# RTC_and_EEPROM.net
KiCad netlist of a schematic drawn in Altium Designer
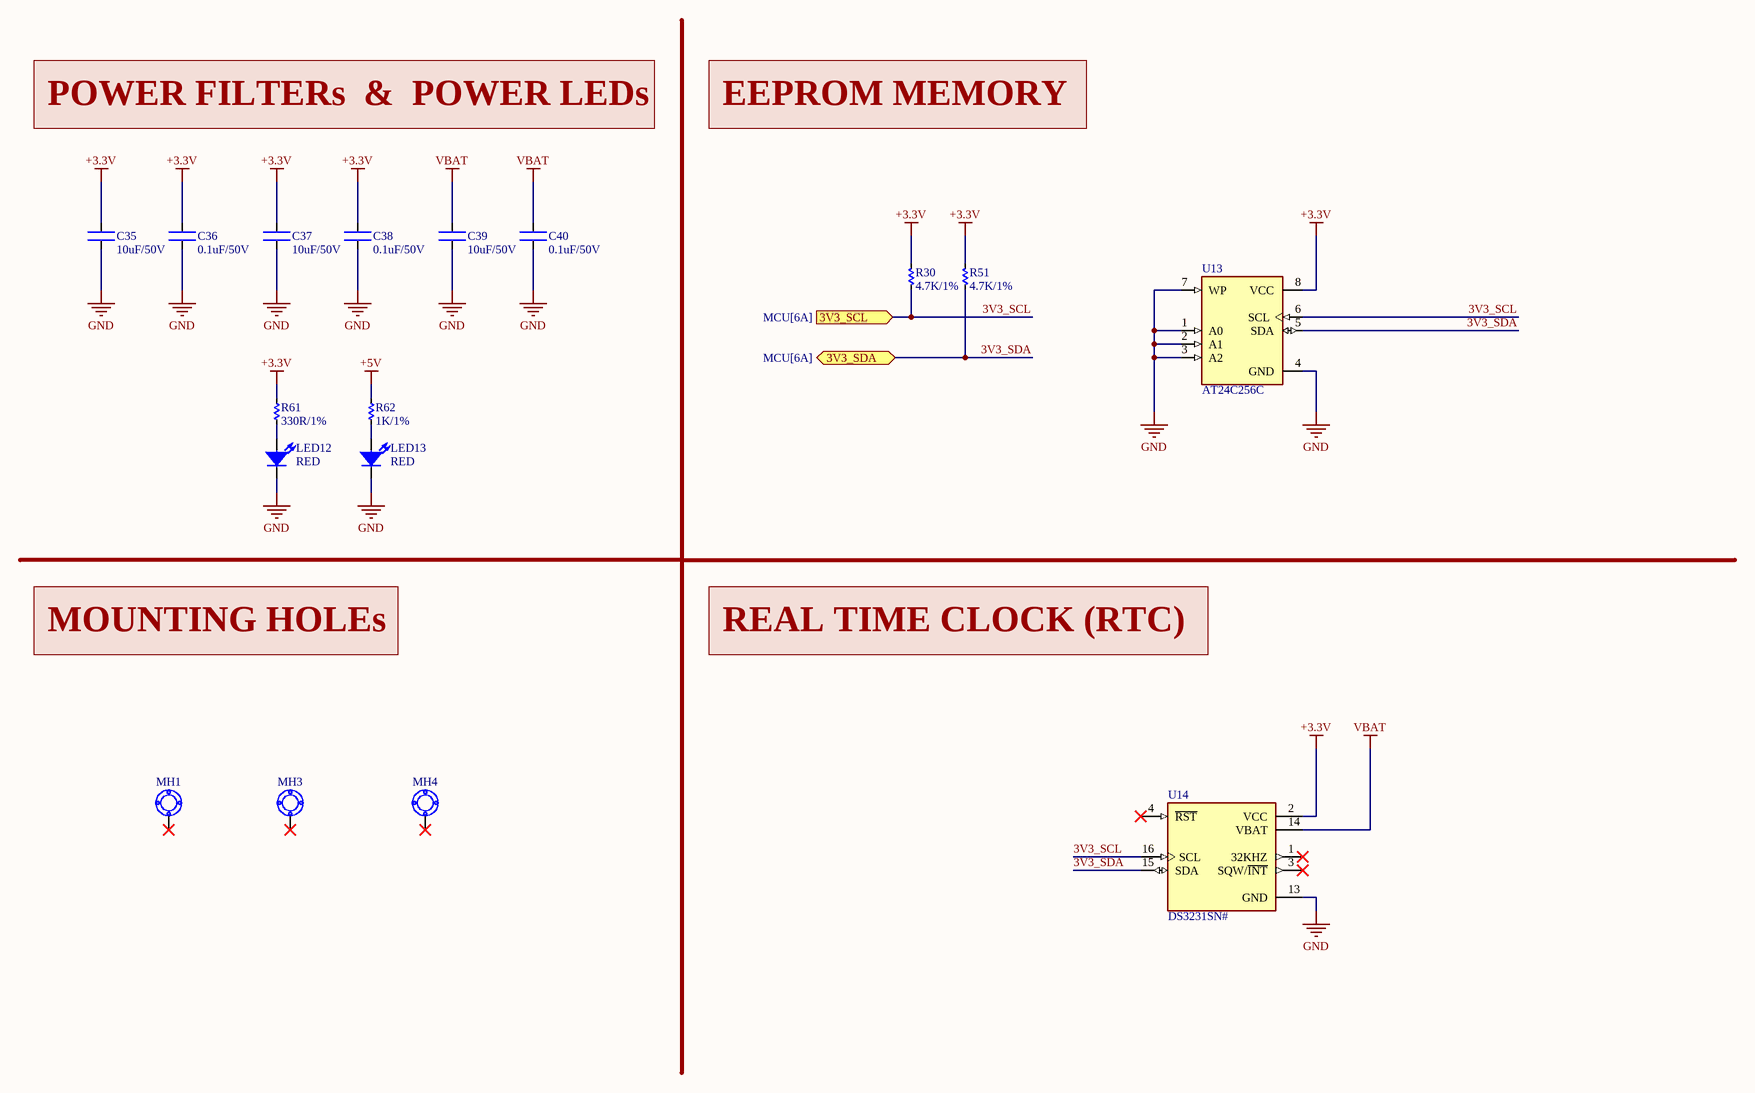
[diagram p0: RTC_and_EEPROM.SchDoc]

(export (version "E")
  (design (tool "Eeschema 10.0.6"))
  (components
    (comp (ref "C35")
      (value "10uF/50V")
      (footprint "CAP - 0603")
      (description "CAPACITOR SMD - KEMET")
      (libsource (lib "NewLibrary") (part "CAPACITOR"))
    )
    (comp (ref "C36")
      (value "0.1uF/50V")
      (footprint "CAP - 0603")
      (description "CAPACITOR SMD - KEMET")
      (libsource (lib "NewLibrary") (part "CAPACITOR"))
    )
    (comp (ref "C37")
      (value "10uF/50V")
      (footprint "CAP - 0603")
      (description "CAPACITOR SMD - KEMET")
      (libsource (lib "NewLibrary") (part "CAPACITOR"))
    )
    (comp (ref "C38")
      (value "0.1uF/50V")
      (footprint "CAP - 0603")
      (description "CAPACITOR SMD - KEMET")
      (libsource (lib "NewLibrary") (part "CAPACITOR"))
    )
    (comp (ref "C39")
      (value "10uF/50V")
      (footprint "CAP - 0603")
      (description "CAPACITOR SMD - KEMET")
      (libsource (lib "NewLibrary") (part "CAPACITOR"))
    )
    (comp (ref "C40")
      (value "0.1uF/50V")
      (footprint "CAP - 0603")
      (description "CAPACITOR SMD - KEMET")
      (libsource (lib "NewLibrary") (part "CAPACITOR"))
    )
    (comp (ref "LED12")
      (value "RED")
      (footprint "RED_LED_0603")
      (description "LED SMD")
      (libsource (lib "NewLibrary") (part "LED_SMD"))
    )
    (comp (ref "LED13")
      (value "RED")
      (footprint "RED_LED_0603")
      (description "LED SMD")
      (libsource (lib "NewLibrary") (part "LED_SMD"))
    )
    (comp (ref "MH1")
      (value "MOUNTING HOLE")
      (footprint "Mounting hole_2")
      (description "Mounting hole")
      (libsource (lib "NewLibrary") (part "MOUNTING HOLE"))
    )
    (comp (ref "MH3")
      (value "MOUNTING HOLE")
      (footprint "Mounting hole_2")
      (description "Mounting hole")
      (libsource (lib "NewLibrary") (part "MOUNTING HOLE"))
    )
    (comp (ref "MH4")
      (value "MOUNTING HOLE")
      (footprint "Mounting hole_2")
      (description "Mounting hole")
      (libsource (lib "NewLibrary") (part "MOUNTING HOLE"))
    )
    (comp (ref "R30")
      (value "4.7K/1%")
      (footprint "RES - 0603")
      (description "Resistor SMD - YAGEO")
      (libsource (lib "NewLibrary") (part "RESISTOR"))
    )
    (comp (ref "R51")
      (value "4.7K/1%")
      (footprint "RES - 0603")
      (description "Resistor SMD - YAGEO")
      (libsource (lib "NewLibrary") (part "RESISTOR"))
    )
    (comp (ref "R61")
      (value "330R/1%")
      (footprint "RES - 0603")
      (description "Resistor SMD - YAGEO")
      (libsource (lib "NewLibrary") (part "RESISTOR"))
    )
    (comp (ref "R62")
      (value "1K/1%")
      (footprint "RES - 0603")
      (description "Resistor SMD - YAGEO")
      (libsource (lib "NewLibrary") (part "RESISTOR"))
    )
    (comp (ref "U13")
      (value "AT24C256C")
      (footprint "SOIC-8")
      (description "EEPROM Memory IC 256Kb (32K x 8), I2C Protocol")
      (libsource (lib "NewLibrary") (part "AT24C256C"))
    )
    (comp (ref "U14")
      (value "DS3231SN#")
      (footprint "SOIC -16")
      (description "Extremely Accurate I²C-Integrated RTC/TCXO/Crystal")
      (libsource (lib "NewLibrary") (part "DS3231SN#"))
    )
  )
  (nets
    (net (code "1") (name "+3.3V") (class "Default")
      (node (ref "C35") (pin "2") (pinfunction "2_2") (pintype "passive"))
      (node (ref "C36") (pin "2") (pinfunction "2_2") (pintype "passive"))
      (node (ref "C37") (pin "2") (pinfunction "2_2") (pintype "passive"))
      (node (ref "C38") (pin "2") (pinfunction "2_2") (pintype "passive"))
      (node (ref "R30") (pin "2") (pinfunction "2_2") (pintype "passive"))
      (node (ref "R51") (pin "2") (pinfunction "2_2") (pintype "passive"))
      (node (ref "R61") (pin "1") (pinfunction "1_1") (pintype "passive"))
      (node (ref "U13") (pin "8") (pinfunction "VCC_8") (pintype "power_in"))
      (node (ref "U14") (pin "2") (pinfunction "VCC_2") (pintype "power_in"))
    )
    (net (code "2") (name "+5V") (class "Default")
      (node (ref "R62") (pin "1") (pinfunction "1_1") (pintype "passive"))
    )
    (net (code "3") (name "/3V3_SCL") (class "Default")
      (node (ref "R30") (pin "1") (pinfunction "1_1") (pintype "passive"))
      (node (ref "U13") (pin "6") (pinfunction "SCL_6") (pintype "input"))
      (node (ref "U14") (pin "16") (pinfunction "SCL_16") (pintype "input"))
    )
    (net (code "4") (name "/3V3_SDA") (class "Default")
      (node (ref "R51") (pin "1") (pinfunction "1_1") (pintype "passive"))
      (node (ref "U13") (pin "5") (pinfunction "SDA_5") (pintype "bidirectional"))
      (node (ref "U14") (pin "15") (pinfunction "SDA_15") (pintype "bidirectional"))
    )
    (net (code "5") (name "GND") (class "Default")
      (node (ref "C35") (pin "1") (pinfunction "1_1") (pintype "passive"))
      (node (ref "C36") (pin "1") (pinfunction "1_1") (pintype "passive"))
      (node (ref "C37") (pin "1") (pinfunction "1_1") (pintype "passive"))
      (node (ref "C38") (pin "1") (pinfunction "1_1") (pintype "passive"))
      (node (ref "C39") (pin "1") (pinfunction "1_1") (pintype "passive"))
      (node (ref "C40") (pin "1") (pinfunction "1_1") (pintype "passive"))
      (node (ref "LED12") (pin "2") (pinfunction "2_2") (pintype "passive"))
      (node (ref "LED13") (pin "2") (pinfunction "2_2") (pintype "passive"))
      (node (ref "U13") (pin "1") (pinfunction "A0_1") (pintype "input"))
      (node (ref "U13") (pin "2") (pinfunction "A1_2") (pintype "input"))
      (node (ref "U13") (pin "3") (pinfunction "A2_3") (pintype "input"))
      (node (ref "U13") (pin "4") (pinfunction "GND_4") (pintype "power_in"))
      (node (ref "U13") (pin "7") (pinfunction "WP_7") (pintype "input"))
      (node (ref "U14") (pin "13") (pinfunction "GND_13") (pintype "power_in"))
    )
    (net (code "6") (name "Net-(LED12-Pad1)") (class "Default")
      (node (ref "LED12") (pin "1") (pinfunction "1_1") (pintype "passive"))
      (node (ref "R61") (pin "2") (pinfunction "2_2") (pintype "passive"))
    )
    (net (code "7") (name "Net-(LED13-Pad1)") (class "Default")
      (node (ref "LED13") (pin "1") (pinfunction "1_1") (pintype "passive"))
      (node (ref "R62") (pin "2") (pinfunction "2_2") (pintype "passive"))
    )
    (net (code "8") (name "VBAT") (class "Default")
      (node (ref "C39") (pin "2") (pinfunction "2_2") (pintype "passive"))
      (node (ref "C40") (pin "2") (pinfunction "2_2") (pintype "passive"))
      (node (ref "U14") (pin "14") (pinfunction "VBAT_14") (pintype "power_in"))
    )
    (net (code "9") (name "unconnected-(MH1-76-Pad1)") (class "Default")
      (node (ref "MH1") (pin "1") (pinfunction "76_1") (pintype "passive+no_connect"))
    )
    (net (code "10") (name "unconnected-(MH3-76-Pad1)") (class "Default")
      (node (ref "MH3") (pin "1") (pinfunction "76_1") (pintype "passive+no_connect"))
    )
    (net (code "11") (name "unconnected-(MH4-76-Pad1)") (class "Default")
      (node (ref "MH4") (pin "1") (pinfunction "76_1") (pintype "passive+no_connect"))
    )
    (net (code "12") (name "unconnected-(U14-32KHZ-Pad1)") (class "Default")
      (node (ref "U14") (pin "1") (pinfunction "32KHZ_1") (pintype "output+no_connect"))
    )
    (net (code "13") (name "unconnected-(U14-SQW{slash}~{INT}-Pad3)") (class "Default")
      (node (ref "U14") (pin "3") (pinfunction "SQW/~{INT}_3") (pintype "output+no_connect"))
    )
    (net (code "14") (name "unconnected-(U14-~{RST}-Pad4)") (class "Default")
      (node (ref "U14") (pin "4") (pinfunction "~{RST}_4") (pintype "input+no_connect"))
    )
  )
)
